# redox-light-right.net
KiCad netlist of a schematic drawn in EAGLE
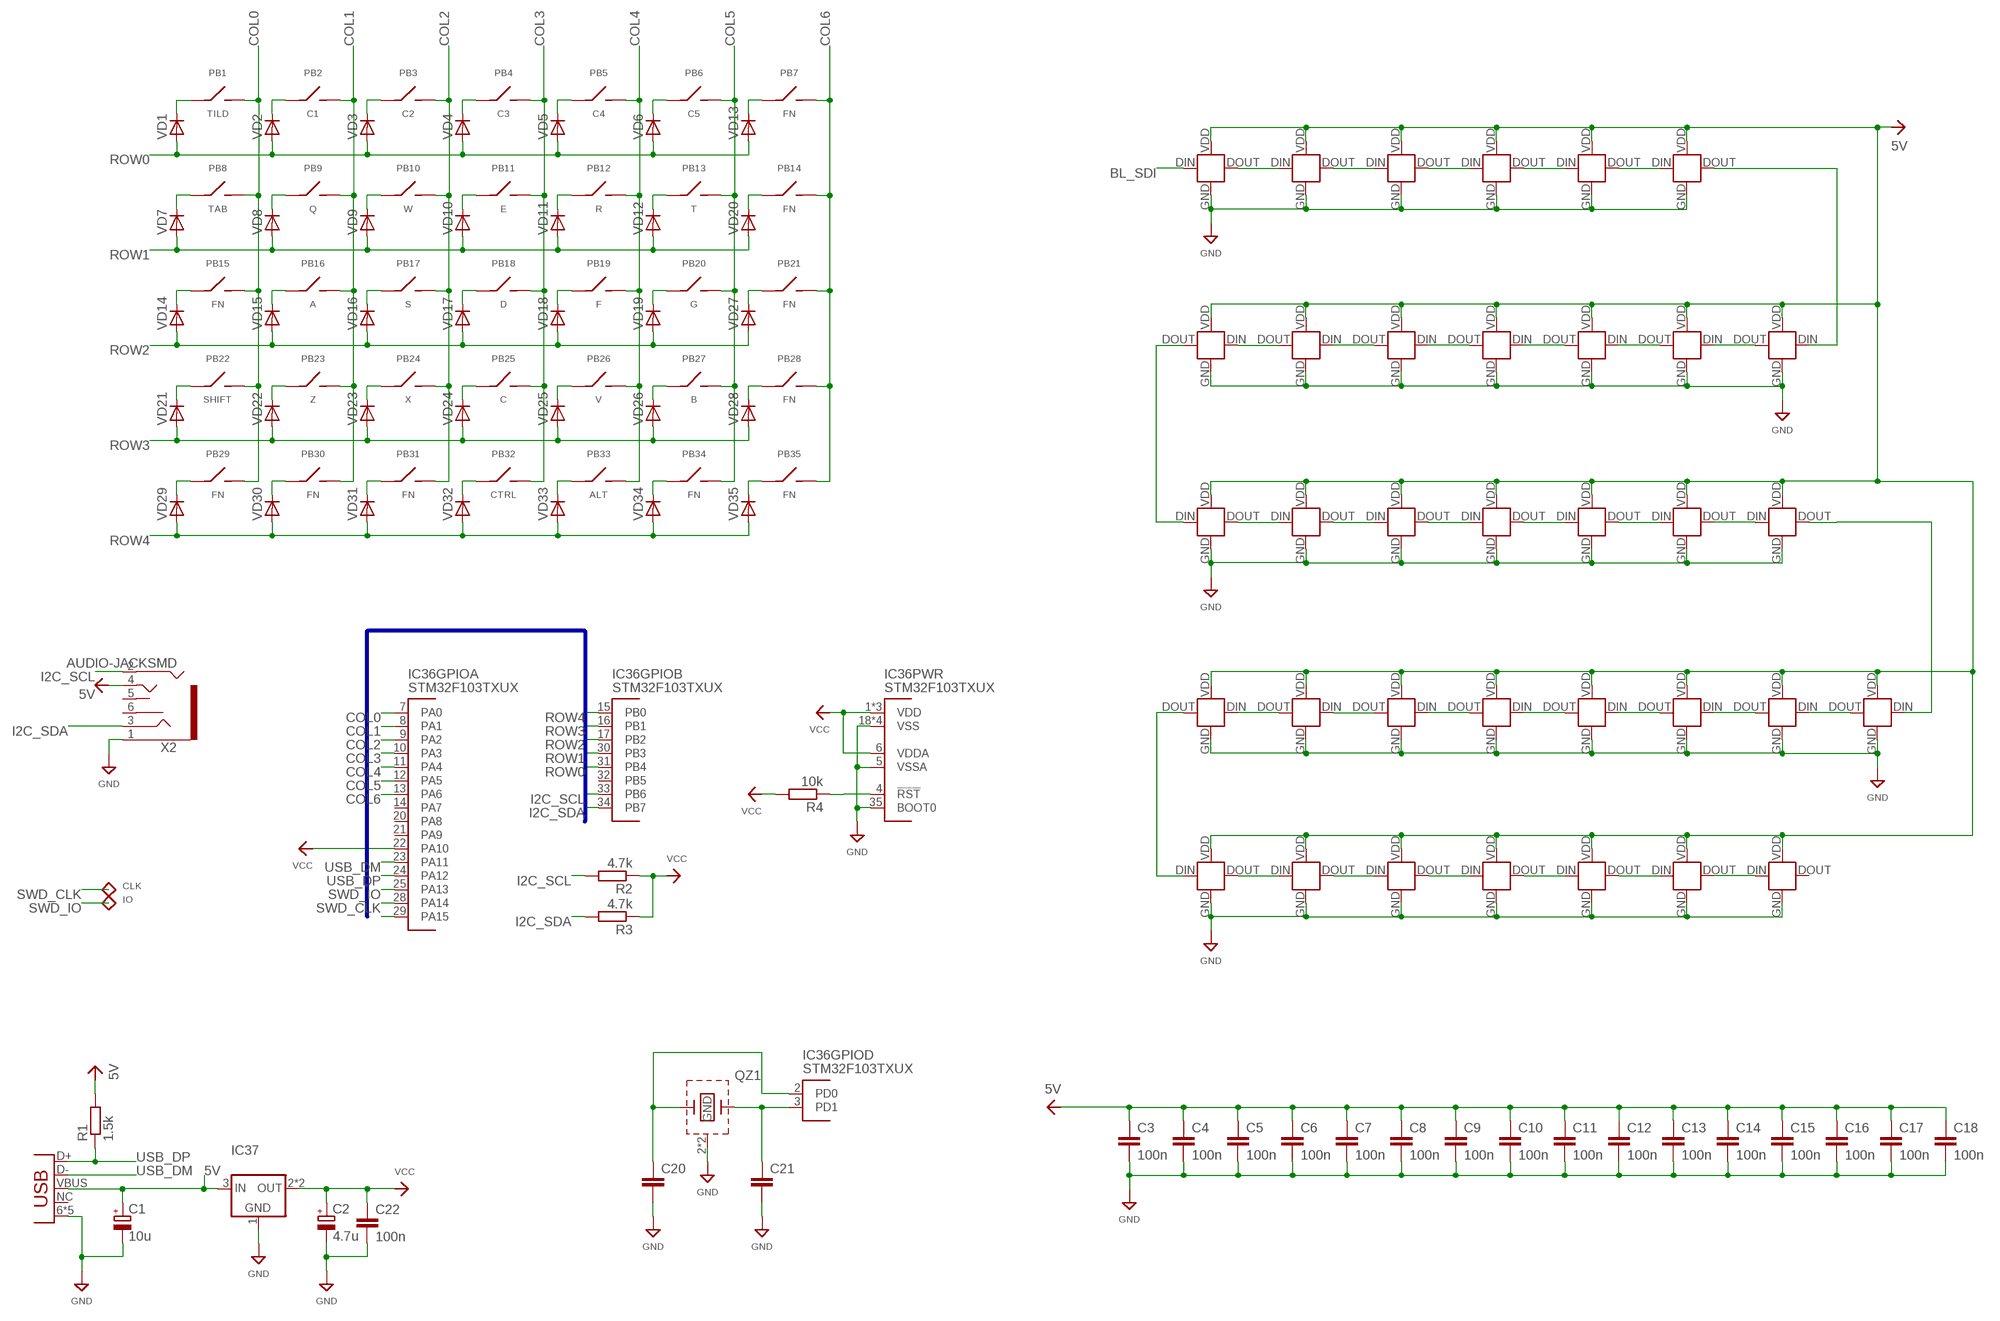
[diagram p0: schematic, sheet 1]

(export (version "E")
  (design (tool "Eeschema 10.0.6"))
  (components
    (comp (ref "C1")
      (value "10u")
      (footprint "eagle-import:SMC_A")
      (libsource (lib "eagle-import") (part "CPOL-EUSMCA"))
    )
    (comp (ref "C2")
      (value "4.7u")
      (footprint "eagle-import:SMC_A")
      (libsource (lib "eagle-import") (part "CPOL-EUSMCA"))
    )
    (comp (ref "C3")
      (value "100n")
      (footprint "eagle-import:R0402")
      (libsource (lib "eagle-import") (part "CAP0402"))
    )
    (comp (ref "C4")
      (value "100n")
      (footprint "eagle-import:R0402")
      (libsource (lib "eagle-import") (part "CAP0402"))
    )
    (comp (ref "C5")
      (value "100n")
      (footprint "eagle-import:R0402")
      (libsource (lib "eagle-import") (part "CAP0402"))
    )
    (comp (ref "C6")
      (value "100n")
      (footprint "eagle-import:R0402")
      (libsource (lib "eagle-import") (part "CAP0402"))
    )
    (comp (ref "C7")
      (value "100n")
      (footprint "eagle-import:R0402")
      (libsource (lib "eagle-import") (part "CAP0402"))
    )
    (comp (ref "C8")
      (value "100n")
      (footprint "eagle-import:R0402")
      (libsource (lib "eagle-import") (part "CAP0402"))
    )
    (comp (ref "C9")
      (value "100n")
      (footprint "eagle-import:R0402")
      (libsource (lib "eagle-import") (part "CAP0402"))
    )
    (comp (ref "C10")
      (value "100n")
      (footprint "eagle-import:R0402")
      (libsource (lib "eagle-import") (part "CAP0402"))
    )
    (comp (ref "C11")
      (value "100n")
      (footprint "eagle-import:R0402")
      (libsource (lib "eagle-import") (part "CAP0402"))
    )
    (comp (ref "C12")
      (value "100n")
      (footprint "eagle-import:R0402")
      (libsource (lib "eagle-import") (part "CAP0402"))
    )
    (comp (ref "C13")
      (value "100n")
      (footprint "eagle-import:R0402")
      (libsource (lib "eagle-import") (part "CAP0402"))
    )
    (comp (ref "C14")
      (value "100n")
      (footprint "eagle-import:R0402")
      (libsource (lib "eagle-import") (part "CAP0402"))
    )
    (comp (ref "C15")
      (value "100n")
      (footprint "eagle-import:R0402")
      (libsource (lib "eagle-import") (part "CAP0402"))
    )
    (comp (ref "C16")
      (value "100n")
      (footprint "eagle-import:R0402")
      (libsource (lib "eagle-import") (part "CAP0402"))
    )
    (comp (ref "C17")
      (value "100n")
      (footprint "eagle-import:R0402")
      (libsource (lib "eagle-import") (part "CAP0402"))
    )
    (comp (ref "C18")
      (value "100n")
      (footprint "eagle-import:R0402")
      (libsource (lib "eagle-import") (part "CAP0402"))
    )
    (comp (ref "C20")
      (value "CAP0402")
      (footprint "eagle-import:R0402")
      (libsource (lib "eagle-import") (part "CAP0402"))
    )
    (comp (ref "C21")
      (value "CAP0402")
      (footprint "eagle-import:R0402")
      (libsource (lib "eagle-import") (part "CAP0402"))
    )
    (comp (ref "C22")
      (value "100n")
      (footprint "eagle-import:R0402")
      (libsource (lib "eagle-import") (part "CAP0402"))
    )
    (comp (ref "IC1")
      (value "SK68XX-MINI")
      (footprint "eagle-import:SK68XX-MINI")
      (libsource (lib "eagle-import") (part "SK68XX-MINI"))
    )
    (comp (ref "IC2")
      (value "SK68XX-MINI")
      (footprint "eagle-import:SK68XX-MINI")
      (libsource (lib "eagle-import") (part "SK68XX-MINI"))
    )
    (comp (ref "IC3")
      (value "SK68XX-MINI")
      (footprint "eagle-import:SK68XX-MINI")
      (libsource (lib "eagle-import") (part "SK68XX-MINI"))
    )
    (comp (ref "IC4")
      (value "SK68XX-MINI")
      (footprint "eagle-import:SK68XX-MINI")
      (libsource (lib "eagle-import") (part "SK68XX-MINI"))
    )
    (comp (ref "IC5")
      (value "SK68XX-MINI")
      (footprint "eagle-import:SK68XX-MINI")
      (libsource (lib "eagle-import") (part "SK68XX-MINI"))
    )
    (comp (ref "IC6")
      (value "SK68XX-MINI")
      (footprint "eagle-import:SK68XX-MINI")
      (libsource (lib "eagle-import") (part "SK68XX-MINI"))
    )
    (comp (ref "IC7")
      (value "SK68XX-MINI")
      (footprint "eagle-import:SK68XX-MINI")
      (fields (field (name "SPICEPREFIX") "E"))
      (libsource (lib "eagle-import") (part "SK68XX-MINI"))
    )
    (comp (ref "IC8")
      (value "SK68XX-MINI")
      (footprint "eagle-import:SK68XX-MINI")
      (fields (field (name "SPICEPREFIX") "E"))
      (libsource (lib "eagle-import") (part "SK68XX-MINI"))
    )
    (comp (ref "IC9")
      (value "SK68XX-MINI")
      (footprint "eagle-import:SK68XX-MINI")
      (fields (field (name "SPICEPREFIX") "E"))
      (libsource (lib "eagle-import") (part "SK68XX-MINI"))
    )
    (comp (ref "IC10")
      (value "SK68XX-MINI")
      (footprint "eagle-import:SK68XX-MINI")
      (fields (field (name "SPICEPREFIX") "E"))
      (libsource (lib "eagle-import") (part "SK68XX-MINI"))
    )
    (comp (ref "IC11")
      (value "SK68XX-MINI")
      (footprint "eagle-import:SK68XX-MINI")
      (fields (field (name "SPICEPREFIX") "E"))
      (libsource (lib "eagle-import") (part "SK68XX-MINI"))
    )
    (comp (ref "IC12")
      (value "SK68XX-MINI")
      (footprint "eagle-import:SK68XX-MINI")
      (fields (field (name "SPICEPREFIX") "E"))
      (libsource (lib "eagle-import") (part "SK68XX-MINI"))
    )
    (comp (ref "IC13")
      (value "SK68XX-MINI")
      (footprint "eagle-import:SK68XX-MINI")
      (fields (field (name "SPICEPREFIX") "E"))
      (libsource (lib "eagle-import") (part "SK68XX-MINI"))
    )
    (comp (ref "IC14")
      (value "SK68XX-MINI")
      (footprint "eagle-import:SK68XX-MINI")
      (libsource (lib "eagle-import") (part "SK68XX-MINI"))
    )
    (comp (ref "IC15")
      (value "SK68XX-MINI")
      (footprint "eagle-import:SK68XX-MINI")
      (libsource (lib "eagle-import") (part "SK68XX-MINI"))
    )
    (comp (ref "IC16")
      (value "SK68XX-MINI")
      (footprint "eagle-import:SK68XX-MINI")
      (libsource (lib "eagle-import") (part "SK68XX-MINI"))
    )
    (comp (ref "IC17")
      (value "SK68XX-MINI")
      (footprint "eagle-import:SK68XX-MINI")
      (libsource (lib "eagle-import") (part "SK68XX-MINI"))
    )
    (comp (ref "IC18")
      (value "SK68XX-MINI")
      (footprint "eagle-import:SK68XX-MINI")
      (libsource (lib "eagle-import") (part "SK68XX-MINI"))
    )
    (comp (ref "IC19")
      (value "SK68XX-MINI")
      (footprint "eagle-import:SK68XX-MINI")
      (libsource (lib "eagle-import") (part "SK68XX-MINI"))
    )
    (comp (ref "IC20")
      (value "SK68XX-MINI")
      (footprint "eagle-import:SK68XX-MINI")
      (libsource (lib "eagle-import") (part "SK68XX-MINI"))
    )
    (comp (ref "IC21")
      (value "SK68XX-MINI")
      (footprint "eagle-import:SK68XX-MINI")
      (libsource (lib "eagle-import") (part "SK68XX-MINI"))
    )
    (comp (ref "IC22")
      (value "SK68XX-MINI")
      (footprint "eagle-import:SK68XX-MINI")
      (libsource (lib "eagle-import") (part "SK68XX-MINI"))
    )
    (comp (ref "IC23")
      (value "SK68XX-MINI")
      (footprint "eagle-import:SK68XX-MINI")
      (libsource (lib "eagle-import") (part "SK68XX-MINI"))
    )
    (comp (ref "IC24")
      (value "SK68XX-MINI")
      (footprint "eagle-import:SK68XX-MINI")
      (libsource (lib "eagle-import") (part "SK68XX-MINI"))
    )
    (comp (ref "IC25")
      (value "SK68XX-MINI")
      (footprint "eagle-import:SK68XX-MINI")
      (libsource (lib "eagle-import") (part "SK68XX-MINI"))
    )
    (comp (ref "IC26")
      (value "SK68XX-MINI")
      (footprint "eagle-import:SK68XX-MINI")
      (libsource (lib "eagle-import") (part "SK68XX-MINI"))
    )
    (comp (ref "IC27")
      (value "SK68XX-MINI")
      (footprint "eagle-import:SK68XX-MINI")
      (libsource (lib "eagle-import") (part "SK68XX-MINI"))
    )
    (comp (ref "IC28")
      (value "SK68XX-MINI")
      (footprint "eagle-import:SK68XX-MINI")
      (libsource (lib "eagle-import") (part "SK68XX-MINI"))
    )
    (comp (ref "IC29")
      (value "SK68XX-MINI")
      (footprint "eagle-import:SK68XX-MINI")
      (libsource (lib "eagle-import") (part "SK68XX-MINI"))
    )
    (comp (ref "IC30")
      (value "SK68XX-MINI")
      (footprint "eagle-import:SK68XX-MINI")
      (libsource (lib "eagle-import") (part "SK68XX-MINI"))
    )
    (comp (ref "IC31")
      (value "SK68XX-MINI")
      (footprint "eagle-import:SK68XX-MINI")
      (libsource (lib "eagle-import") (part "SK68XX-MINI"))
    )
    (comp (ref "IC32")
      (value "SK68XX-MINI")
      (footprint "eagle-import:SK68XX-MINI")
      (libsource (lib "eagle-import") (part "SK68XX-MINI"))
    )
    (comp (ref "IC33")
      (value "SK68XX-MINI")
      (footprint "eagle-import:SK68XX-MINI")
      (libsource (lib "eagle-import") (part "SK68XX-MINI"))
    )
    (comp (ref "IC34")
      (value "SK68XX-MINI")
      (footprint "eagle-import:SK68XX-MINI")
      (libsource (lib "eagle-import") (part "SK68XX-MINI"))
    )
    (comp (ref "IC35")
      (value "SK68XX-MINI")
      (footprint "eagle-import:SK68XX-MINI")
      (libsource (lib "eagle-import") (part "SK68XX-MINI"))
    )
    (comp (ref "IC36")
      (value "STM32F103TXUX")
      (footprint "eagle-import:QFN-36")
      (libsource (lib "eagle-import") (part "STM32F103TXUX"))
    )
    (comp (ref "IC37")
      (value "LM1117")
      (footprint "eagle-import:SOT89")
      (libsource (lib "eagle-import") (part "LM1117"))
    )
    (comp (ref "PB1")
      (value "TILD")
      (footprint "eagle-import:CHERRY-MX-KAILH")
      (libsource (lib "eagle-import") (part "CHERRY-MX-KAILH"))
    )
    (comp (ref "PB2")
      (value "C1")
      (footprint "eagle-import:CHERRY-MX-KAILH")
      (libsource (lib "eagle-import") (part "CHERRY-MX-KAILH"))
    )
    (comp (ref "PB3")
      (value "C2")
      (footprint "eagle-import:CHERRY-MX-KAILH")
      (libsource (lib "eagle-import") (part "CHERRY-MX-KAILH"))
    )
    (comp (ref "PB4")
      (value "C3")
      (footprint "eagle-import:CHERRY-MX-KAILH")
      (libsource (lib "eagle-import") (part "CHERRY-MX-KAILH"))
    )
    (comp (ref "PB5")
      (value "C4")
      (footprint "eagle-import:CHERRY-MX-KAILH")
      (libsource (lib "eagle-import") (part "CHERRY-MX-KAILH"))
    )
    (comp (ref "PB6")
      (value "C5")
      (footprint "eagle-import:CHERRY-MX-KAILH")
      (libsource (lib "eagle-import") (part "CHERRY-MX-KAILH"))
    )
    (comp (ref "PB7")
      (value "FN")
      (footprint "eagle-import:CHERRY-MX-KAILH")
      (libsource (lib "eagle-import") (part "CHERRY-MX-KAILH"))
    )
    (comp (ref "PB8")
      (value "TAB")
      (footprint "eagle-import:CHERRY-MX-KAILH")
      (libsource (lib "eagle-import") (part "CHERRY-MX-KAILH"))
    )
    (comp (ref "PB9")
      (value "Q")
      (footprint "eagle-import:CHERRY-MX-KAILH")
      (libsource (lib "eagle-import") (part "CHERRY-MX-KAILH"))
    )
    (comp (ref "PB10")
      (value "W")
      (footprint "eagle-import:CHERRY-MX-KAILH")
      (libsource (lib "eagle-import") (part "CHERRY-MX-KAILH"))
    )
    (comp (ref "PB11")
      (value "E")
      (footprint "eagle-import:CHERRY-MX-KAILH")
      (libsource (lib "eagle-import") (part "CHERRY-MX-KAILH"))
    )
    (comp (ref "PB12")
      (value "R")
      (footprint "eagle-import:CHERRY-MX-KAILH")
      (libsource (lib "eagle-import") (part "CHERRY-MX-KAILH"))
    )
    (comp (ref "PB13")
      (value "T")
      (footprint "eagle-import:CHERRY-MX-KAILH")
      (libsource (lib "eagle-import") (part "CHERRY-MX-KAILH"))
    )
    (comp (ref "PB14")
      (value "FN")
      (footprint "eagle-import:CHERRY-MX-KAILH")
      (libsource (lib "eagle-import") (part "CHERRY-MX-KAILH"))
    )
    (comp (ref "PB15")
      (value "FN")
      (footprint "eagle-import:CHERRY-MX-KAILH")
      (libsource (lib "eagle-import") (part "CHERRY-MX-KAILH"))
    )
    (comp (ref "PB16")
      (value "A")
      (footprint "eagle-import:CHERRY-MX-KAILH")
      (libsource (lib "eagle-import") (part "CHERRY-MX-KAILH"))
    )
    (comp (ref "PB17")
      (value "S")
      (footprint "eagle-import:CHERRY-MX-KAILH")
      (libsource (lib "eagle-import") (part "CHERRY-MX-KAILH"))
    )
    (comp (ref "PB18")
      (value "D")
      (footprint "eagle-import:CHERRY-MX-KAILH")
      (libsource (lib "eagle-import") (part "CHERRY-MX-KAILH"))
    )
    (comp (ref "PB19")
      (value "F")
      (footprint "eagle-import:CHERRY-MX-KAILH")
      (libsource (lib "eagle-import") (part "CHERRY-MX-KAILH"))
    )
    (comp (ref "PB20")
      (value "G")
      (footprint "eagle-import:CHERRY-MX-KAILH")
      (libsource (lib "eagle-import") (part "CHERRY-MX-KAILH"))
    )
    (comp (ref "PB21")
      (value "FN")
      (footprint "eagle-import:CHERRY-MX-KAILH")
      (libsource (lib "eagle-import") (part "CHERRY-MX-KAILH"))
    )
    (comp (ref "PB22")
      (value "SHIFT")
      (footprint "eagle-import:CHERRY-MX-KAILH")
      (libsource (lib "eagle-import") (part "CHERRY-MX-KAILH"))
    )
    (comp (ref "PB23")
      (value "Z")
      (footprint "eagle-import:CHERRY-MX-KAILH")
      (libsource (lib "eagle-import") (part "CHERRY-MX-KAILH"))
    )
    (comp (ref "PB24")
      (value "X")
      (footprint "eagle-import:CHERRY-MX-KAILH")
      (libsource (lib "eagle-import") (part "CHERRY-MX-KAILH"))
    )
    (comp (ref "PB25")
      (value "C")
      (footprint "eagle-import:CHERRY-MX-KAILH")
      (libsource (lib "eagle-import") (part "CHERRY-MX-KAILH"))
    )
    (comp (ref "PB26")
      (value "V")
      (footprint "eagle-import:CHERRY-MX-KAILH")
      (libsource (lib "eagle-import") (part "CHERRY-MX-KAILH"))
    )
    (comp (ref "PB27")
      (value "B")
      (footprint "eagle-import:CHERRY-MX-KAILH")
      (libsource (lib "eagle-import") (part "CHERRY-MX-KAILH"))
    )
    (comp (ref "PB28")
      (value "FN")
      (footprint "eagle-import:CHERRY-MX-KAILH")
      (libsource (lib "eagle-import") (part "CHERRY-MX-KAILH"))
    )
    (comp (ref "PB29")
      (value "FN")
      (footprint "eagle-import:CHERRY-MX-KAILH")
      (libsource (lib "eagle-import") (part "CHERRY-MX-KAILH"))
    )
    (comp (ref "PB30")
      (value "FN")
      (footprint "eagle-import:CHERRY-MX-KAILH")
      (libsource (lib "eagle-import") (part "CHERRY-MX-KAILH"))
    )
    (comp (ref "PB31")
      (value "FN")
      (footprint "eagle-import:CHERRY-MX-KAILH")
      (libsource (lib "eagle-import") (part "CHERRY-MX-KAILH"))
    )
    (comp (ref "PB32")
      (value "CTRL")
      (footprint "eagle-import:CHERRY-MX-KAILH")
      (libsource (lib "eagle-import") (part "CHERRY-MX-KAILH"))
    )
    (comp (ref "PB33")
      (value "ALT")
      (footprint "eagle-import:CHERRY-MX-KAILH")
      (libsource (lib "eagle-import") (part "CHERRY-MX-KAILH"))
    )
    (comp (ref "PB34")
      (value "FN")
      (footprint "eagle-import:CHERRY-MX-KAILH")
      (libsource (lib "eagle-import") (part "CHERRY-MX-KAILH"))
    )
    (comp (ref "PB35")
      (value "FN")
      (footprint "eagle-import:CHERRY-MX-KAILH")
      (libsource (lib "eagle-import") (part "CHERRY-MX-KAILH"))
    )
    (comp (ref "QZ1")
      (value "QUARTZ_GND3225")
      (footprint "eagle-import:3225")
      (libsource (lib "eagle-import") (part "QUARTZ_GND3225"))
    )
    (comp (ref "R1")
      (value "1.5k")
      (footprint "eagle-import:R0402")
      (libsource (lib "eagle-import") (part "RESR0402"))
    )
    (comp (ref "R2")
      (value "4.7k")
      (footprint "eagle-import:R0402")
      (libsource (lib "eagle-import") (part "RESR0402"))
    )
    (comp (ref "R3")
      (value "4.7k")
      (footprint "eagle-import:R0402")
      (libsource (lib "eagle-import") (part "RESR0402"))
    )
    (comp (ref "R4")
      (value "10k")
      (footprint "eagle-import:R0402")
      (libsource (lib "eagle-import") (part "RESR0402"))
    )
    (comp (ref "TP1")
      (value "CLK")
      (footprint "eagle-import:TP10R")
      (libsource (lib "eagle-import") (part "TP10R"))
    )
    (comp (ref "TP2")
      (value "IO")
      (footprint "eagle-import:TP10R")
      (libsource (lib "eagle-import") (part "TP10R"))
    )
    (comp (ref "VD1")
      (value "DIODE-SOD123")
      (footprint "eagle-import:SOD123")
      (libsource (lib "eagle-import") (part "DIODE-SOD123"))
    )
    (comp (ref "VD2")
      (value "DIODE-SOD123")
      (footprint "eagle-import:SOD123")
      (libsource (lib "eagle-import") (part "DIODE-SOD123"))
    )
    (comp (ref "VD3")
      (value "DIODE-SOD123")
      (footprint "eagle-import:SOD123")
      (libsource (lib "eagle-import") (part "DIODE-SOD123"))
    )
    (comp (ref "VD4")
      (value "DIODE-SOD123")
      (footprint "eagle-import:SOD123")
      (libsource (lib "eagle-import") (part "DIODE-SOD123"))
    )
    (comp (ref "VD5")
      (value "DIODE-SOD123")
      (footprint "eagle-import:SOD123")
      (libsource (lib "eagle-import") (part "DIODE-SOD123"))
    )
    (comp (ref "VD6")
      (value "DIODE-SOD123")
      (footprint "eagle-import:SOD123")
      (libsource (lib "eagle-import") (part "DIODE-SOD123"))
    )
    (comp (ref "VD7")
      (value "DIODE-SOD123")
      (footprint "eagle-import:SOD123")
      (libsource (lib "eagle-import") (part "DIODE-SOD123"))
    )
    (comp (ref "VD8")
      (value "DIODE-SOD123")
      (footprint "eagle-import:SOD123")
      (libsource (lib "eagle-import") (part "DIODE-SOD123"))
    )
    (comp (ref "VD9")
      (value "DIODE-SOD123")
      (footprint "eagle-import:SOD123")
      (libsource (lib "eagle-import") (part "DIODE-SOD123"))
    )
    (comp (ref "VD10")
      (value "DIODE-SOD123")
      (footprint "eagle-import:SOD123")
      (libsource (lib "eagle-import") (part "DIODE-SOD123"))
    )
    (comp (ref "VD11")
      (value "DIODE-SOD123")
      (footprint "eagle-import:SOD123")
      (libsource (lib "eagle-import") (part "DIODE-SOD123"))
    )
    (comp (ref "VD12")
      (value "DIODE-SOD123")
      (footprint "eagle-import:SOD123")
      (libsource (lib "eagle-import") (part "DIODE-SOD123"))
    )
    (comp (ref "VD13")
      (value "DIODE-SOD123")
      (footprint "eagle-import:SOD123")
      (libsource (lib "eagle-import") (part "DIODE-SOD123"))
    )
    (comp (ref "VD14")
      (value "DIODE-SOD123")
      (footprint "eagle-import:SOD123")
      (libsource (lib "eagle-import") (part "DIODE-SOD123"))
    )
    (comp (ref "VD15")
      (value "DIODE-SOD123")
      (footprint "eagle-import:SOD123")
      (libsource (lib "eagle-import") (part "DIODE-SOD123"))
    )
    (comp (ref "VD16")
      (value "DIODE-SOD123")
      (footprint "eagle-import:SOD123")
      (libsource (lib "eagle-import") (part "DIODE-SOD123"))
    )
    (comp (ref "VD17")
      (value "DIODE-SOD123")
      (footprint "eagle-import:SOD123")
      (libsource (lib "eagle-import") (part "DIODE-SOD123"))
    )
    (comp (ref "VD18")
      (value "DIODE-SOD123")
      (footprint "eagle-import:SOD123")
      (libsource (lib "eagle-import") (part "DIODE-SOD123"))
    )
    (comp (ref "VD19")
      (value "DIODE-SOD123")
      (footprint "eagle-import:SOD123")
      (libsource (lib "eagle-import") (part "DIODE-SOD123"))
    )
    (comp (ref "VD20")
      (value "DIODE-SOD123")
      (footprint "eagle-import:SOD123")
      (libsource (lib "eagle-import") (part "DIODE-SOD123"))
    )
    (comp (ref "VD21")
      (value "DIODE-SOD123")
      (footprint "eagle-import:SOD123")
      (libsource (lib "eagle-import") (part "DIODE-SOD123"))
    )
    (comp (ref "VD22")
      (value "DIODE-SOD123")
      (footprint "eagle-import:SOD123")
      (libsource (lib "eagle-import") (part "DIODE-SOD123"))
    )
    (comp (ref "VD23")
      (value "DIODE-SOD123")
      (footprint "eagle-import:SOD123")
      (libsource (lib "eagle-import") (part "DIODE-SOD123"))
    )
    (comp (ref "VD24")
      (value "DIODE-SOD123")
      (footprint "eagle-import:SOD123")
      (libsource (lib "eagle-import") (part "DIODE-SOD123"))
    )
    (comp (ref "VD25")
      (value "DIODE-SOD123")
      (footprint "eagle-import:SOD123")
      (libsource (lib "eagle-import") (part "DIODE-SOD123"))
    )
    (comp (ref "VD26")
      (value "DIODE-SOD123")
      (footprint "eagle-import:SOD123")
      (libsource (lib "eagle-import") (part "DIODE-SOD123"))
    )
    (comp (ref "VD27")
      (value "DIODE-SOD123")
      (footprint "eagle-import:SOD123")
      (libsource (lib "eagle-import") (part "DIODE-SOD123"))
    )
    (comp (ref "VD28")
      (value "DIODE-SOD123")
      (footprint "eagle-import:SOD123")
      (libsource (lib "eagle-import") (part "DIODE-SOD123"))
    )
    (comp (ref "VD29")
      (value "DIODE-SOD123")
      (footprint "eagle-import:SOD123")
      (libsource (lib "eagle-import") (part "DIODE-SOD123"))
    )
    (comp (ref "VD30")
      (value "DIODE-SOD123")
      (footprint "eagle-import:SOD123")
      (libsource (lib "eagle-import") (part "DIODE-SOD123"))
    )
    (comp (ref "VD31")
      (value "DIODE-SOD123")
      (footprint "eagle-import:SOD123")
      (libsource (lib "eagle-import") (part "DIODE-SOD123"))
    )
    (comp (ref "VD32")
      (value "DIODE-SOD123")
      (footprint "eagle-import:SOD123")
      (libsource (lib "eagle-import") (part "DIODE-SOD123"))
    )
    (comp (ref "VD33")
      (value "DIODE-SOD123")
      (footprint "eagle-import:SOD123")
      (libsource (lib "eagle-import") (part "DIODE-SOD123"))
    )
    (comp (ref "VD34")
      (value "DIODE-SOD123")
      (footprint "eagle-import:SOD123")
      (libsource (lib "eagle-import") (part "DIODE-SOD123"))
    )
    (comp (ref "VD35")
      (value "DIODE-SOD123")
      (footprint "eagle-import:SOD123")
      (libsource (lib "eagle-import") (part "DIODE-SOD123"))
    )
    (comp (ref "X1")
      (value "USBMICRO_B")
      (footprint "eagle-import:USB_MICROB")
      (libsource (lib "eagle-import") (part "USBMICRO_B"))
    )
    (comp (ref "X2")
      (value "AUDIO-JACKSMD")
      (footprint "eagle-import:PJ-342")
      (libsource (lib "eagle-import") (part "AUDIO-JACKSMD"))
    )
  )
  (nets
    (net (code "1") (name "/BL_SDI") (class "Default")
      (node (ref "IC1") (pin "DIN") (pinfunction "DIN_DIN") (pintype "input"))
      (node (ref "IC36") (pin "29") (pinfunction "PA15_29") (pintype "bidirectional"))
    )
    (net (code "2") (name "/COL0") (class "Default")
      (node (ref "IC36") (pin "7") (pinfunction "PA0_7") (pintype "bidirectional"))
      (node (ref "PB1") (pin "2") (pinfunction "2_2") (pintype "bidirectional"))
      (node (ref "PB15") (pin "2") (pinfunction "2_2") (pintype "bidirectional"))
      (node (ref "PB22") (pin "2") (pinfunction "2_2") (pintype "bidirectional"))
      (node (ref "PB29") (pin "2") (pinfunction "2_2") (pintype "bidirectional"))
      (node (ref "PB8") (pin "2") (pinfunction "2_2") (pintype "bidirectional"))
    )
    (net (code "3") (name "/COL1") (class "Default")
      (node (ref "IC36") (pin "8") (pinfunction "PA1_8") (pintype "bidirectional"))
      (node (ref "PB16") (pin "2") (pinfunction "2_2") (pintype "bidirectional"))
      (node (ref "PB2") (pin "2") (pinfunction "2_2") (pintype "bidirectional"))
      (node (ref "PB23") (pin "2") (pinfunction "2_2") (pintype "bidirectional"))
      (node (ref "PB30") (pin "2") (pinfunction "2_2") (pintype "bidirectional"))
      (node (ref "PB9") (pin "2") (pinfunction "2_2") (pintype "bidirectional"))
    )
    (net (code "4") (name "/COL2") (class "Default")
      (node (ref "IC36") (pin "9") (pinfunction "PA2_9") (pintype "bidirectional"))
      (node (ref "PB10") (pin "2") (pinfunction "2_2") (pintype "bidirectional"))
      (node (ref "PB17") (pin "2") (pinfunction "2_2") (pintype "bidirectional"))
      (node (ref "PB24") (pin "2") (pinfunction "2_2") (pintype "bidirectional"))
      (node (ref "PB3") (pin "2") (pinfunction "2_2") (pintype "bidirectional"))
      (node (ref "PB31") (pin "2") (pinfunction "2_2") (pintype "bidirectional"))
    )
    (net (code "5") (name "/COL3") (class "Default")
      (node (ref "IC36") (pin "10") (pinfunction "PA3_10") (pintype "bidirectional"))
      (node (ref "PB11") (pin "2") (pinfunction "2_2") (pintype "bidirectional"))
      (node (ref "PB18") (pin "2") (pinfunction "2_2") (pintype "bidirectional"))
      (node (ref "PB25") (pin "2") (pinfunction "2_2") (pintype "bidirectional"))
      (node (ref "PB32") (pin "2") (pinfunction "2_2") (pintype "bidirectional"))
      (node (ref "PB4") (pin "2") (pinfunction "2_2") (pintype "bidirectional"))
    )
    (net (code "6") (name "/COL4") (class "Default")
      (node (ref "IC36") (pin "11") (pinfunction "PA4_11") (pintype "bidirectional"))
      (node (ref "PB12") (pin "2") (pinfunction "2_2") (pintype "bidirectional"))
      (node (ref "PB19") (pin "2") (pinfunction "2_2") (pintype "bidirectional"))
      (node (ref "PB26") (pin "2") (pinfunction "2_2") (pintype "bidirectional"))
      (node (ref "PB33") (pin "2") (pinfunction "2_2") (pintype "bidirectional"))
      (node (ref "PB5") (pin "2") (pinfunction "2_2") (pintype "bidirectional"))
    )
    (net (code "7") (name "/COL5") (class "Default")
      (node (ref "IC36") (pin "12") (pinfunction "PA5_12") (pintype "bidirectional"))
      (node (ref "PB13") (pin "2") (pinfunction "2_2") (pintype "bidirectional"))
      (node (ref "PB20") (pin "2") (pinfunction "2_2") (pintype "bidirectional"))
      (node (ref "PB27") (pin "2") (pinfunction "2_2") (pintype "bidirectional"))
      (node (ref "PB34") (pin "2") (pinfunction "2_2") (pintype "bidirectional"))
      (node (ref "PB6") (pin "2") (pinfunction "2_2") (pintype "bidirectional"))
    )
    (net (code "8") (name "/COL6") (class "Default")
      (node (ref "IC36") (pin "13") (pinfunction "PA6_13") (pintype "bidirectional"))
      (node (ref "PB14") (pin "2") (pinfunction "2_2") (pintype "bidirectional"))
      (node (ref "PB21") (pin "2") (pinfunction "2_2") (pintype "bidirectional"))
      (node (ref "PB28") (pin "2") (pinfunction "2_2") (pintype "bidirectional"))
      (node (ref "PB35") (pin "2") (pinfunction "2_2") (pintype "bidirectional"))
      (node (ref "PB7") (pin "2") (pinfunction "2_2") (pintype "bidirectional"))
    )
    (net (code "9") (name "/I2C_SCL") (class "Default")
      (node (ref "IC36") (pin "33") (pinfunction "PB6_33") (pintype "bidirectional"))
      (node (ref "R2") (pin "2") (pinfunction "2_2") (pintype "passive"))
      (node (ref "X2") (pin "2") (pinfunction "2_2") (pintype "bidirectional"))
    )
    (net (code "10") (name "/I2C_SDA") (class "Default")
      (node (ref "IC36") (pin "34") (pinfunction "PB7_34") (pintype "bidirectional"))
      (node (ref "R3") (pin "2") (pinfunction "2_2") (pintype "passive"))
      (node (ref "X2") (pin "3") (pinfunction "3_3") (pintype "bidirectional"))
    )
    (net (code "11") (name "/ROW0") (class "Default")
      (node (ref "IC36") (pin "31") (pinfunction "PB4_31") (pintype "bidirectional"))
      (node (ref "VD1") (pin "A") (pinfunction "A_A") (pintype "passive"))
      (node (ref "VD13") (pin "A") (pinfunction "A_A") (pintype "passive"))
      (node (ref "VD2") (pin "A") (pinfunction "A_A") (pintype "passive"))
      (node (ref "VD3") (pin "A") (pinfunction "A_A") (pintype "passive"))
      (node (ref "VD4") (pin "A") (pinfunction "A_A") (pintype "passive"))
      (node (ref "VD5") (pin "A") (pinfunction "A_A") (pintype "passive"))
      (node (ref "VD6") (pin "A") (pinfunction "A_A") (pintype "passive"))
    )
    (net (code "12") (name "/ROW1") (class "Default")
      (node (ref "IC36") (pin "30") (pinfunction "PB3_30") (pintype "bidirectional"))
      (node (ref "VD10") (pin "A") (pinfunction "A_A") (pintype "passive"))
      (node (ref "VD11") (pin "A") (pinfunction "A_A") (pintype "passive"))
      (node (ref "VD12") (pin "A") (pinfunction "A_A") (pintype "passive"))
      (node (ref "VD20") (pin "A") (pinfunction "A_A") (pintype "passive"))
      (node (ref "VD7") (pin "A") (pinfunction "A_A") (pintype "passive"))
      (node (ref "VD8") (pin "A") (pinfunction "A_A") (pintype "passive"))
      (node (ref "VD9") (pin "A") (pinfunction "A_A") (pintype "passive"))
    )
    (net (code "13") (name "/ROW2") (class "Default")
      (node (ref "IC36") (pin "17") (pinfunction "PB2_17") (pintype "bidirectional"))
      (node (ref "VD14") (pin "A") (pinfunction "A_A") (pintype "passive"))
      (node (ref "VD15") (pin "A") (pinfunction "A_A") (pintype "passive"))
      (node (ref "VD16") (pin "A") (pinfunction "A_A") (pintype "passive"))
      (node (ref "VD17") (pin "A") (pinfunction "A_A") (pintype "passive"))
      (node (ref "VD18") (pin "A") (pinfunction "A_A") (pintype "passive"))
      (node (ref "VD19") (pin "A") (pinfunction "A_A") (pintype "passive"))
      (node (ref "VD27") (pin "A") (pinfunction "A_A") (pintype "passive"))
    )
    (net (code "14") (name "/ROW3") (class "Default")
      (node (ref "IC36") (pin "16") (pinfunction "PB1_16") (pintype "bidirectional"))
      (node (ref "VD21") (pin "A") (pinfunction "A_A") (pintype "passive"))
      (node (ref "VD22") (pin "A") (pinfunction "A_A") (pintype "passive"))
      (node (ref "VD23") (pin "A") (pinfunction "A_A") (pintype "passive"))
      (node (ref "VD24") (pin "A") (pinfunction "A_A") (pintype "passive"))
      (node (ref "VD25") (pin "A") (pinfunction "A_A") (pintype "passive"))
      (node (ref "VD26") (pin "A") (pinfunction "A_A") (pintype "passive"))
      (node (ref "VD28") (pin "A") (pinfunction "A_A") (pintype "passive"))
    )
    (net (code "15") (name "/ROW4") (class "Default")
      (node (ref "IC36") (pin "15") (pinfunction "PB0_15") (pintype "bidirectional"))
      (node (ref "VD29") (pin "A") (pinfunction "A_A") (pintype "passive"))
      (node (ref "VD30") (pin "A") (pinfunction "A_A") (pintype "passive"))
      (node (ref "VD31") (pin "A") (pinfunction "A_A") (pintype "passive"))
      (node (ref "VD32") (pin "A") (pinfunction "A_A") (pintype "passive"))
      (node (ref "VD33") (pin "A") (pinfunction "A_A") (pintype "passive"))
      (node (ref "VD34") (pin "A") (pinfunction "A_A") (pintype "passive"))
      (node (ref "VD35") (pin "A") (pinfunction "A_A") (pintype "passive"))
    )
    (net (code "16") (name "/SWD_CLK") (class "Default")
      (node (ref "IC36") (pin "28") (pinfunction "PA14_28") (pintype "bidirectional"))
      (node (ref "TP1") (pin "TP") (pinfunction "TEST_TP") (pintype "bidirectional"))
    )
    (net (code "17") (name "/SWD_IO") (class "Default")
      (node (ref "IC36") (pin "25") (pinfunction "PA13_25") (pintype "bidirectional"))
      (node (ref "TP2") (pin "TP") (pinfunction "TEST_TP") (pintype "bidirectional"))
    )
    (net (code "18") (name "/USB_DM") (class "Default")
      (node (ref "IC36") (pin "23") (pinfunction "PA11_23") (pintype "bidirectional"))
      (node (ref "X1") (pin "D-") (pinfunction "D-_D-") (pintype "bidirectional"))
    )
    (net (code "19") (name "/USB_DP") (class "Default")
      (node (ref "IC36") (pin "24") (pinfunction "PA12_24") (pintype "bidirectional"))
      (node (ref "R1") (pin "1") (pinfunction "1_1") (pintype "passive"))
      (node (ref "X1") (pin "D+") (pinfunction "D+_D+") (pintype "bidirectional"))
    )
    (net (code "20") (name "5V") (class "Default")
      (node (ref "C1") (pin "+") (pinfunction "+_+") (pintype "passive"))
      (node (ref "C10") (pin "1") (pinfunction "1_1") (pintype "passive"))
      (node (ref "C11") (pin "1") (pinfunction "1_1") (pintype "passive"))
      (node (ref "C12") (pin "1") (pinfunction "1_1") (pintype "passive"))
      (node (ref "C13") (pin "1") (pinfunction "1_1") (pintype "passive"))
      (node (ref "C14") (pin "1") (pinfunction "1_1") (pintype "passive"))
      (node (ref "C15") (pin "1") (pinfunction "1_1") (pintype "passive"))
      (node (ref "C16") (pin "1") (pinfunction "1_1") (pintype "passive"))
      (node (ref "C17") (pin "1") (pinfunction "1_1") (pintype "passive"))
      (node (ref "C18") (pin "1") (pinfunction "1_1") (pintype "passive"))
      (node (ref "C3") (pin "1") (pinfunction "1_1") (pintype "passive"))
      (node (ref "C4") (pin "1") (pinfunction "1_1") (pintype "passive"))
      (node (ref "C5") (pin "1") (pinfunction "1_1") (pintype "passive"))
      (node (ref "C6") (pin "1") (pinfunction "1_1") (pintype "passive"))
      (node (ref "C7") (pin "1") (pinfunction "1_1") (pintype "passive"))
      (node (ref "C8") (pin "1") (pinfunction "1_1") (pintype "passive"))
      (node (ref "C9") (pin "1") (pinfunction "1_1") (pintype "passive"))
      (node (ref "IC1") (pin "VDD") (pinfunction "VCC_VDD") (pintype "power_in"))
      (node (ref "IC10") (pin "VDD") (pinfunction "VCC_VDD") (pintype "power_in"))
      (node (ref "IC11") (pin "VDD") (pinfunction "VCC_VDD") (pintype "power_in"))
      (node (ref "IC12") (pin "VDD") (pinfunction "VCC_VDD") (pintype "power_in"))
      (node (ref "IC13") (pin "VDD") (pinfunction "VCC_VDD") (pintype "power_in"))
      (node (ref "IC14") (pin "VDD") (pinfunction "VCC_VDD") (pintype "power_in"))
      (node (ref "IC15") (pin "VDD") (pinfunction "VCC_VDD") (pintype "power_in"))
      (node (ref "IC16") (pin "VDD") (pinfunction "VCC_VDD") (pintype "power_in"))
      (node (ref "IC17") (pin "VDD") (pinfunction "VCC_VDD") (pintype "power_in"))
      (node (ref "IC18") (pin "VDD") (pinfunction "VCC_VDD") (pintype "power_in"))
      (node (ref "IC19") (pin "VDD") (pinfunction "VCC_VDD") (pintype "power_in"))
      (node (ref "IC2") (pin "VDD") (pinfunction "VCC_VDD") (pintype "power_in"))
      (node (ref "IC20") (pin "VDD") (pinfunction "VCC_VDD") (pintype "power_in"))
      (node (ref "IC21") (pin "VDD") (pinfunction "VCC_VDD") (pintype "power_in"))
      (node (ref "IC22") (pin "VDD") (pinfunction "VCC_VDD") (pintype "power_in"))
      (node (ref "IC23") (pin "VDD") (pinfunction "VCC_VDD") (pintype "power_in"))
      (node (ref "IC24") (pin "VDD") (pinfunction "VCC_VDD") (pintype "power_in"))
      (node (ref "IC25") (pin "VDD") (pinfunction "VCC_VDD") (pintype "power_in"))
      (node (ref "IC26") (pin "VDD") (pinfunction "VCC_VDD") (pintype "power_in"))
      (node (ref "IC27") (pin "VDD") (pinfunction "VCC_VDD") (pintype "power_in"))
      (node (ref "IC28") (pin "VDD") (pinfunction "VCC_VDD") (pintype "power_in"))
      (node (ref "IC29") (pin "VDD") (pinfunction "VCC_VDD") (pintype "power_in"))
      (node (ref "IC3") (pin "VDD") (pinfunction "VCC_VDD") (pintype "power_in"))
      (node (ref "IC30") (pin "VDD") (pinfunction "VCC_VDD") (pintype "power_in"))
      (node (ref "IC31") (pin "VDD") (pinfunction "VCC_VDD") (pintype "power_in"))
      (node (ref "IC32") (pin "VDD") (pinfunction "VCC_VDD") (pintype "power_in"))
      (node (ref "IC33") (pin "VDD") (pinfunction "VCC_VDD") (pintype "power_in"))
      (node (ref "IC34") (pin "VDD") (pinfunction "VCC_VDD") (pintype "power_in"))
      (node (ref "IC35") (pin "VDD") (pinfunction "VCC_VDD") (pintype "power_in"))
      (node (ref "IC37") (pin "3") (pinfunction "IN_3") (pintype "input"))
      (node (ref "IC4") (pin "VDD") (pinfunction "VCC_VDD") (pintype "power_in"))
      (node (ref "IC5") (pin "VDD") (pinfunction "VCC_VDD") (pintype "power_in"))
      (node (ref "IC6") (pin "VDD") (pinfunction "VCC_VDD") (pintype "power_in"))
      (node (ref "IC7") (pin "VDD") (pinfunction "VCC_VDD") (pintype "power_in"))
      (node (ref "IC8") (pin "VDD") (pinfunction "VCC_VDD") (pintype "power_in"))
      (node (ref "IC9") (pin "VDD") (pinfunction "VCC_VDD") (pintype "power_in"))
      (node (ref "R1") (pin "2") (pinfunction "2_2") (pintype "passive"))
      (node (ref "X1") (pin "VBUS") (pinfunction "VBUS_VBUS") (pintype "bidirectional"))
      (node (ref "X2") (pin "4") (pinfunction "4_4") (pintype "bidirectional"))
    )
    (net (code "21") (name "GND") (class "Default")
      (node (ref "C1") (pin "-") (pinfunction "-_-") (pintype "passive"))
      (node (ref "C10") (pin "2") (pinfunction "2_2") (pintype "passive"))
      (node (ref "C11") (pin "2") (pinfunction "2_2") (pintype "passive"))
      (node (ref "C12") (pin "2") (pinfunction "2_2") (pintype "passive"))
      (node (ref "C13") (pin "2") (pinfunction "2_2") (pintype "passive"))
      (node (ref "C14") (pin "2") (pinfunction "2_2") (pintype "passive"))
      (node (ref "C15") (pin "2") (pinfunction "2_2") (pintype "passive"))
      (node (ref "C16") (pin "2") (pinfunction "2_2") (pintype "passive"))
      (node (ref "C17") (pin "2") (pinfunction "2_2") (pintype "passive"))
      (node (ref "C18") (pin "2") (pinfunction "2_2") (pintype "passive"))
      (node (ref "C2") (pin "-") (pinfunction "-_-") (pintype "passive"))
      (node (ref "C20") (pin "2") (pinfunction "2_2") (pintype "passive"))
      (node (ref "C21") (pin "2") (pinfunction "2_2") (pintype "passive"))
      (node (ref "C22") (pin "2") (pinfunction "2_2") (pintype "passive"))
      (node (ref "C3") (pin "2") (pinfunction "2_2") (pintype "passive"))
      (node (ref "C4") (pin "2") (pinfunction "2_2") (pintype "passive"))
      (node (ref "C5") (pin "2") (pinfunction "2_2") (pintype "passive"))
      (node (ref "C6") (pin "2") (pinfunction "2_2") (pintype "passive"))
      (node (ref "C7") (pin "2") (pinfunction "2_2") (pintype "passive"))
      (node (ref "C8") (pin "2") (pinfunction "2_2") (pintype "passive"))
      (node (ref "C9") (pin "2") (pinfunction "2_2") (pintype "passive"))
      (node (ref "IC1") (pin "GND") (pinfunction "GND_GND") (pintype "power_in"))
      (node (ref "IC10") (pin "GND") (pinfunction "GND_GND") (pintype "power_in"))
      (node (ref "IC11") (pin "GND") (pinfunction "GND_GND") (pintype "power_in"))
      (node (ref "IC12") (pin "GND") (pinfunction "GND_GND") (pintype "power_in"))
      (node (ref "IC13") (pin "GND") (pinfunction "GND_GND") (pintype "power_in"))
      (node (ref "IC14") (pin "GND") (pinfunction "GND_GND") (pintype "power_in"))
      (node (ref "IC15") (pin "GND") (pinfunction "GND_GND") (pintype "power_in"))
      (node (ref "IC16") (pin "GND") (pinfunction "GND_GND") (pintype "power_in"))
      (node (ref "IC17") (pin "GND") (pinfunction "GND_GND") (pintype "power_in"))
      (node (ref "IC18") (pin "GND") (pinfunction "GND_GND") (pintype "power_in"))
      (node (ref "IC19") (pin "GND") (pinfunction "GND_GND") (pintype "power_in"))
      (node (ref "IC2") (pin "GND") (pinfunction "GND_GND") (pintype "power_in"))
      (node (ref "IC20") (pin "GND") (pinfunction "GND_GND") (pintype "power_in"))
      (node (ref "IC21") (pin "GND") (pinfunction "GND_GND") (pintype "power_in"))
      (node (ref "IC22") (pin "GND") (pinfunction "GND_GND") (pintype "power_in"))
      (node (ref "IC23") (pin "GND") (pinfunction "GND_GND") (pintype "power_in"))
      (node (ref "IC24") (pin "GND") (pinfunction "GND_GND") (pintype "power_in"))
      (node (ref "IC25") (pin "GND") (pinfunction "GND_GND") (pintype "power_in"))
      (node (ref "IC26") (pin "GND") (pinfunction "GND_GND") (pintype "power_in"))
      (node (ref "IC27") (pin "GND") (pinfunction "GND_GND") (pintype "power_in"))
      (node (ref "IC28") (pin "GND") (pinfunction "GND_GND") (pintype "power_in"))
      (node (ref "IC29") (pin "GND") (pinfunction "GND_GND") (pintype "power_in"))
      (node (ref "IC3") (pin "GND") (pinfunction "GND_GND") (pintype "power_in"))
      (node (ref "IC30") (pin "GND") (pinfunction "GND_GND") (pintype "power_in"))
      (node (ref "IC31") (pin "GND") (pinfunction "GND_GND") (pintype "power_in"))
      (node (ref "IC32") (pin "GND") (pinfunction "GND_GND") (pintype "power_in"))
      (node (ref "IC33") (pin "GND") (pinfunction "GND_GND") (pintype "power_in"))
      (node (ref "IC34") (pin "GND") (pinfunction "GND_GND") (pintype "power_in"))
      (node (ref "IC35") (pin "GND") (pinfunction "GND_GND") (pintype "power_in"))
      (node (ref "IC36") (pin "18") (pinfunction "VSS_18") (pintype "power_in"))
      (node (ref "IC36") (pin "26") (pinfunction "VSS_26") (pintype "power_in"))
      (node (ref "IC36") (pin "35") (pinfunction "BOOT0_35") (pintype "power_in"))
      (node (ref "IC36") (pin "36") (pinfunction "VSS_36") (pintype "power_in"))
      (node (ref "IC36") (pin "5") (pinfunction "VSSA_5") (pintype "power_in"))
      (node (ref "IC36") (pin "PGND") (pinfunction "VSS_PGND") (pintype "power_in"))
      (node (ref "IC37") (pin "1") (pinfunction "GND_1") (pintype "power_in"))
      (node (ref "IC4") (pin "GND") (pinfunction "GND_GND") (pintype "power_in"))
      (node (ref "IC5") (pin "GND") (pinfunction "GND_GND") (pintype "power_in"))
      (node (ref "IC6") (pin "GND") (pinfunction "GND_GND") (pintype "power_in"))
      (node (ref "IC7") (pin "GND") (pinfunction "GND_GND") (pintype "power_in"))
      (node (ref "IC8") (pin "GND") (pinfunction "GND_GND") (pintype "power_in"))
      (node (ref "IC9") (pin "GND") (pinfunction "GND_GND") (pintype "power_in"))
      (node (ref "QZ1") (pin "2") (pinfunction "GND_2") (pintype "bidirectional"))
      (node (ref "QZ1") (pin "4") (pinfunction "GND_4") (pintype "bidirectional"))
      (node (ref "X1") (pin "6") (pinfunction "GND_6") (pintype "bidirectional"))
      (node (ref "X1") (pin "7") (pinfunction "GND_7") (pintype "bidirectional"))
      (node (ref "X1") (pin "8") (pinfunction "GND_8") (pintype "bidirectional"))
      (node (ref "X1") (pin "9") (pinfunction "GND_9") (pintype "bidirectional"))
      (node (ref "X1") (pin "GND") (pinfunction "GND_GND") (pintype "bidirectional"))
      (node (ref "X2") (pin "1") (pinfunction "1_1") (pintype "bidirectional"))
    )
    (net (code "22") (name "Net-(IC1-PadDOUT)") (class "Default")
      (node (ref "IC1") (pin "DOUT") (pinfunction "DOUT_DOUT") (pintype "output"))
      (node (ref "IC2") (pin "DIN") (pinfunction "DIN_DIN") (pintype "input"))
    )
    (net (code "23") (name "Net-(IC2-PadDOUT)") (class "Default")
      (node (ref "IC2") (pin "DOUT") (pinfunction "DOUT_DOUT") (pintype "output"))
      (node (ref "IC3") (pin "DIN") (pinfunction "DIN_DIN") (pintype "input"))
    )
    (net (code "24") (name "Net-(IC3-PadDOUT)") (class "Default")
      (node (ref "IC3") (pin "DOUT") (pinfunction "DOUT_DOUT") (pintype "output"))
      (node (ref "IC4") (pin "DIN") (pinfunction "DIN_DIN") (pintype "input"))
    )
    (net (code "25") (name "Net-(IC4-PadDOUT)") (class "Default")
      (node (ref "IC4") (pin "DOUT") (pinfunction "DOUT_DOUT") (pintype "output"))
      (node (ref "IC5") (pin "DIN") (pinfunction "DIN_DIN") (pintype "input"))
    )
    (net (code "26") (name "Net-(IC5-PadDOUT)") (class "Default")
      (node (ref "IC5") (pin "DOUT") (pinfunction "DOUT_DOUT") (pintype "output"))
      (node (ref "IC6") (pin "DIN") (pinfunction "DIN_DIN") (pintype "input"))
    )
    (net (code "27") (name "Net-(IC6-PadDOUT)") (class "Default")
      (node (ref "IC6") (pin "DOUT") (pinfunction "DOUT_DOUT") (pintype "output"))
      (node (ref "IC7") (pin "DIN") (pinfunction "DIN_DIN") (pintype "input"))
    )
    (net (code "28") (name "Net-(IC7-PadDOUT)") (class "Default")
      (node (ref "IC7") (pin "DOUT") (pinfunction "DOUT_DOUT") (pintype "output"))
      (node (ref "IC8") (pin "DIN") (pinfunction "DIN_DIN") (pintype "input"))
    )
    (net (code "29") (name "Net-(IC8-PadDOUT)") (class "Default")
      (node (ref "IC8") (pin "DOUT") (pinfunction "DOUT_DOUT") (pintype "output"))
      (node (ref "IC9") (pin "DIN") (pinfunction "DIN_DIN") (pintype "input"))
    )
    (net (code "30") (name "Net-(IC10-PadDIN)") (class "Default")
      (node (ref "IC10") (pin "DIN") (pinfunction "DIN_DIN") (pintype "input"))
      (node (ref "IC9") (pin "DOUT") (pinfunction "DOUT_DOUT") (pintype "output"))
    )
    (net (code "31") (name "Net-(IC10-PadDOUT)") (class "Default")
      (node (ref "IC10") (pin "DOUT") (pinfunction "DOUT_DOUT") (pintype "output"))
      (node (ref "IC11") (pin "DIN") (pinfunction "DIN_DIN") (pintype "input"))
    )
    (net (code "32") (name "Net-(IC11-PadDOUT)") (class "Default")
      (node (ref "IC11") (pin "DOUT") (pinfunction "DOUT_DOUT") (pintype "output"))
      (node (ref "IC12") (pin "DIN") (pinfunction "DIN_DIN") (pintype "input"))
    )
    (net (code "33") (name "Net-(IC12-PadDOUT)") (class "Default")
      (node (ref "IC12") (pin "DOUT") (pinfunction "DOUT_DOUT") (pintype "output"))
      (node (ref "IC13") (pin "DIN") (pinfunction "DIN_DIN") (pintype "input"))
    )
    (net (code "34") (name "Net-(IC13-PadDOUT)") (class "Default")
      (node (ref "IC13") (pin "DOUT") (pinfunction "DOUT_DOUT") (pintype "output"))
      (node (ref "IC14") (pin "DIN") (pinfunction "DIN_DIN") (pintype "input"))
    )
    (net (code "35") (name "Net-(IC14-PadDOUT)") (class "Default")
      (node (ref "IC14") (pin "DOUT") (pinfunction "DOUT_DOUT") (pintype "output"))
      (node (ref "IC15") (pin "DIN") (pinfunction "DIN_DIN") (pintype "input"))
    )
    (net (code "36") (name "Net-(IC15-PadDOUT)") (class "Default")
      (node (ref "IC15") (pin "DOUT") (pinfunction "DOUT_DOUT") (pintype "output"))
      (node (ref "IC16") (pin "DIN") (pinfunction "DIN_DIN") (pintype "input"))
    )
    (net (code "37") (name "Net-(IC16-PadDOUT)") (class "Default")
      (node (ref "IC16") (pin "DOUT") (pinfunction "DOUT_DOUT") (pintype "output"))
      (node (ref "IC17") (pin "DIN") (pinfunction "DIN_DIN") (pintype "input"))
    )
    (net (code "38") (name "Net-(IC17-PadDOUT)") (class "Default")
      (node (ref "IC17") (pin "DOUT") (pinfunction "DOUT_DOUT") (pintype "output"))
      (node (ref "IC18") (pin "DIN") (pinfunction "DIN_DIN") (pintype "input"))
    )
    (net (code "39") (name "Net-(IC18-PadDOUT)") (class "Default")
      (node (ref "IC18") (pin "DOUT") (pinfunction "DOUT_DOUT") (pintype "output"))
      (node (ref "IC19") (pin "DIN") (pinfunction "DIN_DIN") (pintype "input"))
    )
    (net (code "40") (name "Net-(IC19-PadDOUT)") (class "Default")
      (node (ref "IC19") (pin "DOUT") (pinfunction "DOUT_DOUT") (pintype "output"))
      (node (ref "IC20") (pin "DIN") (pinfunction "DIN_DIN") (pintype "input"))
    )
    (net (code "41") (name "Net-(IC20-PadDOUT)") (class "Default")
      (node (ref "IC20") (pin "DOUT") (pinfunction "DOUT_DOUT") (pintype "output"))
      (node (ref "IC21") (pin "DIN") (pinfunction "DIN_DIN") (pintype "input"))
    )
    (net (code "42") (name "Net-(IC21-PadDOUT)") (class "Default")
      (node (ref "IC21") (pin "DOUT") (pinfunction "DOUT_DOUT") (pintype "output"))
      (node (ref "IC22") (pin "DIN") (pinfunction "DIN_DIN") (pintype "input"))
    )
    (net (code "43") (name "Net-(IC22-PadDOUT)") (class "Default")
      (node (ref "IC22") (pin "DOUT") (pinfunction "DOUT_DOUT") (pintype "output"))
      (node (ref "IC23") (pin "DIN") (pinfunction "DIN_DIN") (pintype "input"))
    )
    (net (code "44") (name "Net-(IC23-PadDOUT)") (class "Default")
      (node (ref "IC23") (pin "DOUT") (pinfunction "DOUT_DOUT") (pintype "output"))
      (node (ref "IC24") (pin "DIN") (pinfunction "DIN_DIN") (pintype "input"))
    )
    (net (code "45") (name "Net-(IC24-PadDOUT)") (class "Default")
      (node (ref "IC24") (pin "DOUT") (pinfunction "DOUT_DOUT") (pintype "output"))
      (node (ref "IC25") (pin "DIN") (pinfunction "DIN_DIN") (pintype "input"))
    )
    (net (code "46") (name "Net-(IC25-PadDOUT)") (class "Default")
      (node (ref "IC25") (pin "DOUT") (pinfunction "DOUT_DOUT") (pintype "output"))
      (node (ref "IC26") (pin "DIN") (pinfunction "DIN_DIN") (pintype "input"))
    )
    (net (code "47") (name "Net-(IC26-PadDOUT)") (class "Default")
      (node (ref "IC26") (pin "DOUT") (pinfunction "DOUT_DOUT") (pintype "output"))
      (node (ref "IC27") (pin "DIN") (pinfunction "DIN_DIN") (pintype "input"))
    )
    (net (code "48") (name "Net-(IC27-PadDOUT)") (class "Default")
      (node (ref "IC27") (pin "DOUT") (pinfunction "DOUT_DOUT") (pintype "output"))
      (node (ref "IC28") (pin "DIN") (pinfunction "DIN_DIN") (pintype "input"))
    )
    (net (code "49") (name "Net-(IC28-PadDOUT)") (class "Default")
      (node (ref "IC28") (pin "DOUT") (pinfunction "DOUT_DOUT") (pintype "output"))
      (node (ref "IC29") (pin "DIN") (pinfunction "DIN_DIN") (pintype "input"))
    )
    (net (code "50") (name "Net-(IC29-PadDOUT)") (class "Default")
      (node (ref "IC29") (pin "DOUT") (pinfunction "DOUT_DOUT") (pintype "output"))
      (node (ref "IC30") (pin "DIN") (pinfunction "DIN_DIN") (pintype "input"))
    )
    (net (code "51") (name "Net-(IC30-PadDOUT)") (class "Default")
      (node (ref "IC30") (pin "DOUT") (pinfunction "DOUT_DOUT") (pintype "output"))
      (node (ref "IC31") (pin "DIN") (pinfunction "DIN_DIN") (pintype "input"))
    )
    (net (code "52") (name "Net-(IC31-PadDOUT)") (class "Default")
      (node (ref "IC31") (pin "DOUT") (pinfunction "DOUT_DOUT") (pintype "output"))
      (node (ref "IC32") (pin "DIN") (pinfunction "DIN_DIN") (pintype "input"))
    )
    (net (code "53") (name "Net-(IC32-PadDOUT)") (class "Default")
      (node (ref "IC32") (pin "DOUT") (pinfunction "DOUT_DOUT") (pintype "output"))
      (node (ref "IC33") (pin "DIN") (pinfunction "DIN_DIN") (pintype "input"))
    )
    (net (code "54") (name "Net-(IC33-PadDOUT)") (class "Default")
      (node (ref "IC33") (pin "DOUT") (pinfunction "DOUT_DOUT") (pintype "output"))
      (node (ref "IC34") (pin "DIN") (pinfunction "DIN_DIN") (pintype "input"))
    )
    (net (code "55") (name "Net-(IC34-PadDOUT)") (class "Default")
      (node (ref "IC34") (pin "DOUT") (pinfunction "DOUT_DOUT") (pintype "output"))
      (node (ref "IC35") (pin "DIN") (pinfunction "DIN_DIN") (pintype "input"))
    )
    (net (code "56") (name "Net-(IC36C-PD0)") (class "Default")
      (node (ref "C20") (pin "1") (pinfunction "1_1") (pintype "passive"))
      (node (ref "IC36") (pin "2") (pinfunction "PD0_2") (pintype "bidirectional"))
      (node (ref "QZ1") (pin "3") (pinfunction "2_3") (pintype "bidirectional"))
    )
    (net (code "57") (name "Net-(IC36C-PD1)") (class "Default")
      (node (ref "C21") (pin "1") (pinfunction "1_1") (pintype "passive"))
      (node (ref "IC36") (pin "3") (pinfunction "PD1_3") (pintype "bidirectional"))
      (node (ref "QZ1") (pin "1") (pinfunction "1_1") (pintype "bidirectional"))
    )
    (net (code "58") (name "Net-(IC36D-~{RST})") (class "Default")
      (node (ref "IC36") (pin "4") (pinfunction "~{RST}_4") (pintype "power_in"))
      (node (ref "R4") (pin "1") (pinfunction "1_1") (pintype "passive"))
    )
    (net (code "59") (name "Net-(PB1-Pad1)") (class "Default")
      (node (ref "PB1") (pin "1") (pinfunction "1_1") (pintype "bidirectional"))
      (node (ref "VD1") (pin "C") (pinfunction "C_C") (pintype "passive"))
    )
    (net (code "60") (name "Net-(PB2-Pad1)") (class "Default")
      (node (ref "PB2") (pin "1") (pinfunction "1_1") (pintype "bidirectional"))
      (node (ref "VD2") (pin "C") (pinfunction "C_C") (pintype "passive"))
    )
    (net (code "61") (name "Net-(PB3-Pad1)") (class "Default")
      (node (ref "PB3") (pin "1") (pinfunction "1_1") (pintype "bidirectional"))
      (node (ref "VD3") (pin "C") (pinfunction "C_C") (pintype "passive"))
    )
    (net (code "62") (name "Net-(PB4-Pad1)") (class "Default")
      (node (ref "PB4") (pin "1") (pinfunction "1_1") (pintype "bidirectional"))
      (node (ref "VD4") (pin "C") (pinfunction "C_C") (pintype "passive"))
    )
    (net (code "63") (name "Net-(PB5-Pad1)") (class "Default")
      (node (ref "PB5") (pin "1") (pinfunction "1_1") (pintype "bidirectional"))
      (node (ref "VD5") (pin "C") (pinfunction "C_C") (pintype "passive"))
    )
    (net (code "64") (name "Net-(PB6-Pad1)") (class "Default")
      (node (ref "PB6") (pin "1") (pinfunction "1_1") (pintype "bidirectional"))
      (node (ref "VD6") (pin "C") (pinfunction "C_C") (pintype "passive"))
    )
    (net (code "65") (name "Net-(PB7-Pad1)") (class "Default")
      (node (ref "PB7") (pin "1") (pinfunction "1_1") (pintype "bidirectional"))
      (node (ref "VD13") (pin "C") (pinfunction "C_C") (pintype "passive"))
    )
    (net (code "66") (name "Net-(PB8-Pad1)") (class "Default")
      (node (ref "PB8") (pin "1") (pinfunction "1_1") (pintype "bidirectional"))
      (node (ref "VD7") (pin "C") (pinfunction "C_C") (pintype "passive"))
    )
    (net (code "67") (name "Net-(PB9-Pad1)") (class "Default")
      (node (ref "PB9") (pin "1") (pinfunction "1_1") (pintype "bidirectional"))
      (node (ref "VD8") (pin "C") (pinfunction "C_C") (pintype "passive"))
    )
    (net (code "68") (name "Net-(PB10-Pad1)") (class "Default")
      (node (ref "PB10") (pin "1") (pinfunction "1_1") (pintype "bidirectional"))
      (node (ref "VD9") (pin "C") (pinfunction "C_C") (pintype "passive"))
    )
    (net (code "69") (name "Net-(PB11-Pad1)") (class "Default")
      (node (ref "PB11") (pin "1") (pinfunction "1_1") (pintype "bidirectional"))
      (node (ref "VD10") (pin "C") (pinfunction "C_C") (pintype "passive"))
    )
    (net (code "70") (name "Net-(PB12-Pad1)") (class "Default")
      (node (ref "PB12") (pin "1") (pinfunction "1_1") (pintype "bidirectional"))
      (node (ref "VD11") (pin "C") (pinfunction "C_C") (pintype "passive"))
    )
    (net (code "71") (name "Net-(PB13-Pad1)") (class "Default")
      (node (ref "PB13") (pin "1") (pinfunction "1_1") (pintype "bidirectional"))
      (node (ref "VD12") (pin "C") (pinfunction "C_C") (pintype "passive"))
    )
    (net (code "72") (name "Net-(PB14-Pad1)") (class "Default")
      (node (ref "PB14") (pin "1") (pinfunction "1_1") (pintype "bidirectional"))
      (node (ref "VD20") (pin "C") (pinfunction "C_C") (pintype "passive"))
    )
    (net (code "73") (name "Net-(PB15-Pad1)") (class "Default")
      (node (ref "PB15") (pin "1") (pinfunction "1_1") (pintype "bidirectional"))
      (node (ref "VD14") (pin "C") (pinfunction "C_C") (pintype "passive"))
    )
    (net (code "74") (name "Net-(PB16-Pad1)") (class "Default")
      (node (ref "PB16") (pin "1") (pinfunction "1_1") (pintype "bidirectional"))
      (node (ref "VD15") (pin "C") (pinfunction "C_C") (pintype "passive"))
    )
    (net (code "75") (name "Net-(PB17-Pad1)") (class "Default")
      (node (ref "PB17") (pin "1") (pinfunction "1_1") (pintype "bidirectional"))
      (node (ref "VD16") (pin "C") (pinfunction "C_C") (pintype "passive"))
    )
    (net (code "76") (name "Net-(PB18-Pad1)") (class "Default")
      (node (ref "PB18") (pin "1") (pinfunction "1_1") (pintype "bidirectional"))
      (node (ref "VD17") (pin "C") (pinfunction "C_C") (pintype "passive"))
    )
    (net (code "77") (name "Net-(PB19-Pad1)") (class "Default")
      (node (ref "PB19") (pin "1") (pinfunction "1_1") (pintype "bidirectional"))
      (node (ref "VD18") (pin "C") (pinfunction "C_C") (pintype "passive"))
    )
    (net (code "78") (name "Net-(PB20-Pad1)") (class "Default")
      (node (ref "PB20") (pin "1") (pinfunction "1_1") (pintype "bidirectional"))
      (node (ref "VD19") (pin "C") (pinfunction "C_C") (pintype "passive"))
    )
    (net (code "79") (name "Net-(PB21-Pad1)") (class "Default")
      (node (ref "PB21") (pin "1") (pinfunction "1_1") (pintype "bidirectional"))
      (node (ref "VD27") (pin "C") (pinfunction "C_C") (pintype "passive"))
    )
    (net (code "80") (name "Net-(PB22-Pad1)") (class "Default")
      (node (ref "PB22") (pin "1") (pinfunction "1_1") (pintype "bidirectional"))
      (node (ref "VD21") (pin "C") (pinfunction "C_C") (pintype "passive"))
    )
    (net (code "81") (name "Net-(PB23-Pad1)") (class "Default")
      (node (ref "PB23") (pin "1") (pinfunction "1_1") (pintype "bidirectional"))
      (node (ref "VD22") (pin "C") (pinfunction "C_C") (pintype "passive"))
    )
    (net (code "82") (name "Net-(PB24-Pad1)") (class "Default")
      (node (ref "PB24") (pin "1") (pinfunction "1_1") (pintype "bidirectional"))
      (node (ref "VD23") (pin "C") (pinfunction "C_C") (pintype "passive"))
    )
    (net (code "83") (name "Net-(PB25-Pad1)") (class "Default")
      (node (ref "PB25") (pin "1") (pinfunction "1_1") (pintype "bidirectional"))
      (node (ref "VD24") (pin "C") (pinfunction "C_C") (pintype "passive"))
    )
    (net (code "84") (name "Net-(PB26-Pad1)") (class "Default")
      (node (ref "PB26") (pin "1") (pinfunction "1_1") (pintype "bidirectional"))
      (node (ref "VD25") (pin "C") (pinfunction "C_C") (pintype "passive"))
    )
    (net (code "85") (name "Net-(PB27-Pad1)") (class "Default")
      (node (ref "PB27") (pin "1") (pinfunction "1_1") (pintype "bidirectional"))
      (node (ref "VD26") (pin "C") (pinfunction "C_C") (pintype "passive"))
    )
    (net (code "86") (name "Net-(PB28-Pad1)") (class "Default")
      (node (ref "PB28") (pin "1") (pinfunction "1_1") (pintype "bidirectional"))
      (node (ref "VD28") (pin "C") (pinfunction "C_C") (pintype "passive"))
    )
    (net (code "87") (name "Net-(PB29-Pad1)") (class "Default")
      (node (ref "PB29") (pin "1") (pinfunction "1_1") (pintype "bidirectional"))
      (node (ref "VD29") (pin "C") (pinfunction "C_C") (pintype "passive"))
    )
    (net (code "88") (name "Net-(PB30-Pad1)") (class "Default")
      (node (ref "PB30") (pin "1") (pinfunction "1_1") (pintype "bidirectional"))
      (node (ref "VD30") (pin "C") (pinfunction "C_C") (pintype "passive"))
    )
    (net (code "89") (name "Net-(PB31-Pad1)") (class "Default")
      (node (ref "PB31") (pin "1") (pinfunction "1_1") (pintype "bidirectional"))
      (node (ref "VD31") (pin "C") (pinfunction "C_C") (pintype "passive"))
    )
    (net (code "90") (name "Net-(PB32-Pad1)") (class "Default")
      (node (ref "PB32") (pin "1") (pinfunction "1_1") (pintype "bidirectional"))
      (node (ref "VD32") (pin "C") (pinfunction "C_C") (pintype "passive"))
    )
    (net (code "91") (name "Net-(PB33-Pad1)") (class "Default")
      (node (ref "PB33") (pin "1") (pinfunction "1_1") (pintype "bidirectional"))
      (node (ref "VD33") (pin "C") (pinfunction "C_C") (pintype "passive"))
    )
    (net (code "92") (name "Net-(PB34-Pad1)") (class "Default")
      (node (ref "PB34") (pin "1") (pinfunction "1_1") (pintype "bidirectional"))
      (node (ref "VD34") (pin "C") (pinfunction "C_C") (pintype "passive"))
    )
    (net (code "93") (name "Net-(PB35-Pad1)") (class "Default")
      (node (ref "PB35") (pin "1") (pinfunction "1_1") (pintype "bidirectional"))
      (node (ref "VD35") (pin "C") (pinfunction "C_C") (pintype "passive"))
    )
    (net (code "94") (name "VCC") (class "Default")
      (node (ref "C2") (pin "+") (pinfunction "+_+") (pintype "passive"))
      (node (ref "C22") (pin "1") (pinfunction "1_1") (pintype "passive"))
      (node (ref "IC36") (pin "1") (pinfunction "VDD_1") (pintype "power_in"))
      (node (ref "IC36") (pin "19") (pinfunction "VDD_19") (pintype "power_in"))
      (node (ref "IC36") (pin "22") (pinfunction "PA10_22") (pintype "bidirectional"))
      (node (ref "IC36") (pin "27") (pinfunction "VDD_27") (pintype "power_in"))
      (node (ref "IC36") (pin "6") (pinfunction "VDDA_6") (pintype "power_in"))
      (node (ref "IC37") (pin "2") (pinfunction "OUT_2") (pintype "passive"))
      (node (ref "IC37") (pin "4") (pinfunction "OUT_4") (pintype "passive"))
      (node (ref "R2") (pin "1") (pinfunction "1_1") (pintype "passive"))
      (node (ref "R3") (pin "1") (pinfunction "1_1") (pintype "passive"))
      (node (ref "R4") (pin "2") (pinfunction "2_2") (pintype "passive"))
    )
    (net (code "95") (name "unconnected-(IC35-PadDOUT)") (class "Default")
      (node (ref "IC35") (pin "DOUT") (pinfunction "DOUT_DOUT") (pintype "output"))
    )
    (net (code "96") (name "unconnected-(IC36A-PA7-Pad14)") (class "Default")
      (node (ref "IC36") (pin "14") (pinfunction "PA7_14") (pintype "bidirectional"))
    )
    (net (code "97") (name "unconnected-(IC36A-PA8-Pad20)") (class "Default")
      (node (ref "IC36") (pin "20") (pinfunction "PA8_20") (pintype "bidirectional"))
    )
    (net (code "98") (name "unconnected-(IC36A-PA9-Pad21)") (class "Default")
      (node (ref "IC36") (pin "21") (pinfunction "PA9_21") (pintype "bidirectional"))
    )
    (net (code "99") (name "unconnected-(IC36B-PB5-Pad32)") (class "Default")
      (node (ref "IC36") (pin "32") (pinfunction "PB5_32") (pintype "bidirectional"))
    )
    (net (code "100") (name "unconnected-(X1-PadNC)") (class "Default")
      (node (ref "X1") (pin "NC") (pinfunction "NC_NC") (pintype "bidirectional"))
    )
    (net (code "101") (name "unconnected-(X2-Pad5)") (class "Default")
      (node (ref "X2") (pin "5") (pinfunction "5_5") (pintype "bidirectional"))
    )
    (net (code "102") (name "unconnected-(X2-Pad6)") (class "Default")
      (node (ref "X2") (pin "6") (pinfunction "6_6") (pintype "bidirectional"))
    )
  )
)
